# narvi-ctrl.net
KiCad netlist of a schematic drawn in EAGLE
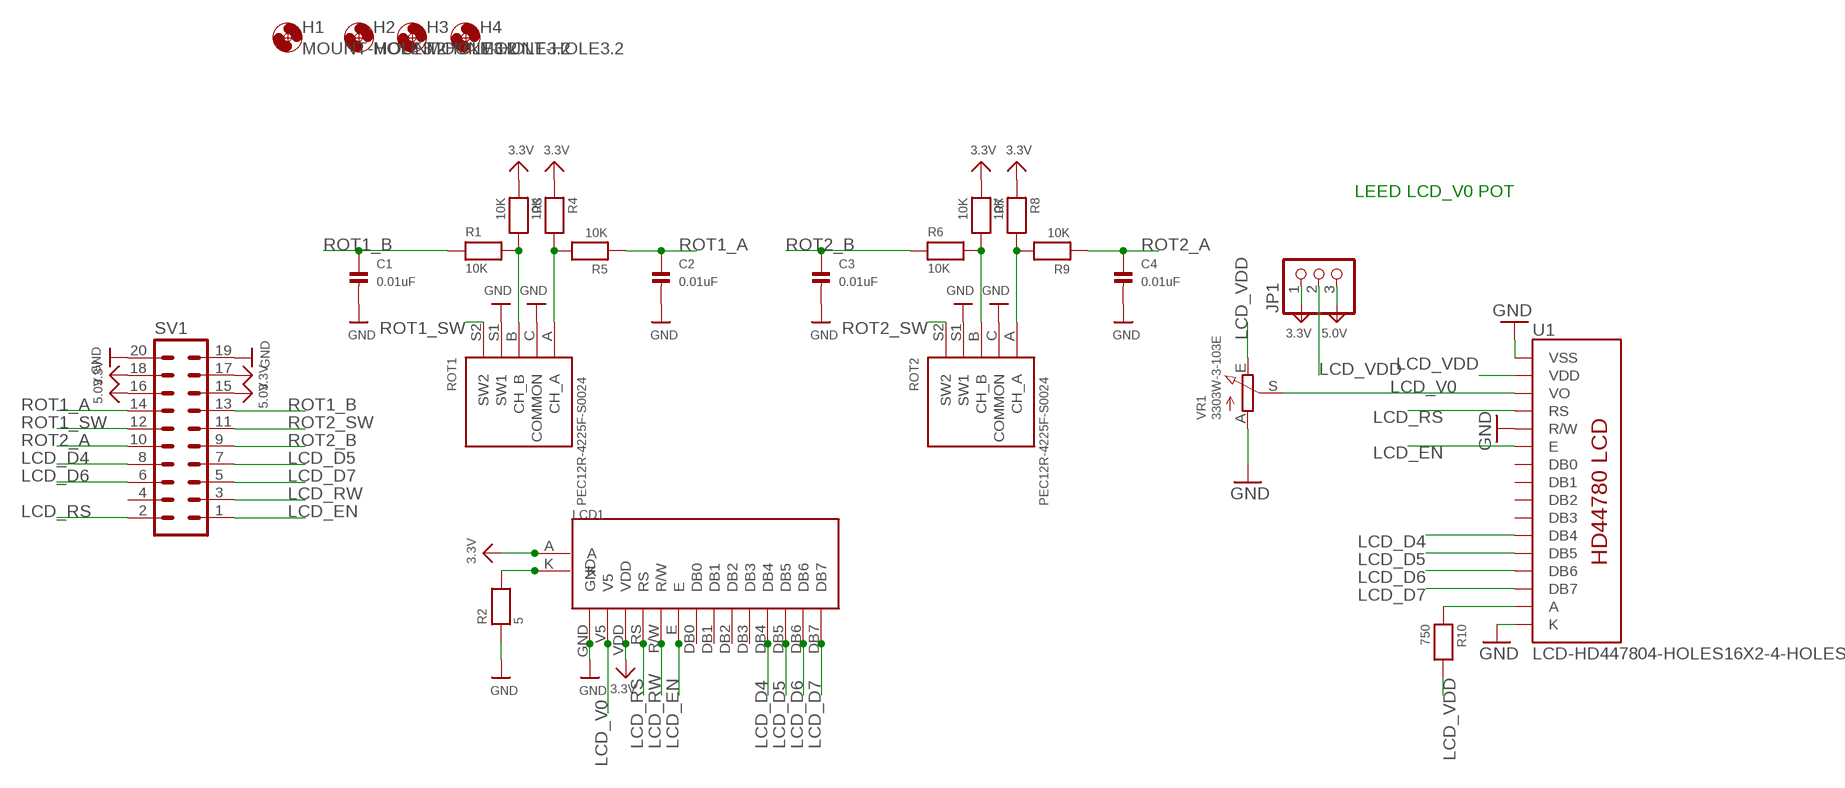
[diagram p0: schematic, sheet 1]

(export (version "E")
  (design (tool "Eeschema 10.0.6"))
  (components
    (comp (ref "C1")
      (value "0.01uF")
      (footprint "eagle-import:0805")
      (libsource (lib "eagle-import") (part "CAP_CERAMIC0805"))
    )
    (comp (ref "C2")
      (value "0.01uF")
      (footprint "eagle-import:0805")
      (libsource (lib "eagle-import") (part "CAP_CERAMIC0805"))
    )
    (comp (ref "C3")
      (value "0.01uF")
      (footprint "eagle-import:0805")
      (libsource (lib "eagle-import") (part "CAP_CERAMIC0805"))
    )
    (comp (ref "C4")
      (value "0.01uF")
      (footprint "eagle-import:0805")
      (libsource (lib "eagle-import") (part "CAP_CERAMIC0805"))
    )
    (comp (ref "H1")
      (value "MOUNT-HOLE3.2")
      (footprint "eagle-import:3,2")
      (libsource (lib "eagle-import") (part "MOUNT-HOLE3.2"))
    )
    (comp (ref "H2")
      (value "MOUNT-HOLE3.2")
      (footprint "eagle-import:3,2")
      (libsource (lib "eagle-import") (part "MOUNT-HOLE3.2"))
    )
    (comp (ref "H3")
      (value "MOUNT-HOLE3.2")
      (footprint "eagle-import:3,2")
      (libsource (lib "eagle-import") (part "MOUNT-HOLE3.2"))
    )
    (comp (ref "H4")
      (value "MOUNT-HOLE3.2")
      (footprint "eagle-import:3,2")
      (libsource (lib "eagle-import") (part "MOUNT-HOLE3.2"))
    )
    (comp (ref "JP1")
      (value "PINHD-1X3")
      (footprint "eagle-import:1X03")
      (libsource (lib "eagle-import") (part "PINHD-1X3"))
    )
    (comp (ref "LCD1")
      (value "NHD-C0220AA-FSW-FTW")
      (footprint "eagle-import:NHD-C0220AA-FSW-FTW")
      (libsource (lib "eagle-import") (part "NHD-C0220AA-FSW-FTW"))
    )
    (comp (ref "R1")
      (value "10K")
      (footprint "eagle-import:_0805")
      (libsource (lib "eagle-import") (part "RESISTOR_0805"))
    )
    (comp (ref "R2")
      (value "5")
      (footprint "eagle-import:_0805")
      (libsource (lib "eagle-import") (part "RESISTOR_0805"))
    )
    (comp (ref "R3")
      (value "10K")
      (footprint "eagle-import:_0805")
      (libsource (lib "eagle-import") (part "RESISTOR_0805"))
    )
    (comp (ref "R4")
      (value "10K")
      (footprint "eagle-import:_0805")
      (libsource (lib "eagle-import") (part "RESISTOR_0805"))
    )
    (comp (ref "R5")
      (value "10K")
      (footprint "eagle-import:_0805")
      (libsource (lib "eagle-import") (part "RESISTOR_0805"))
    )
    (comp (ref "R6")
      (value "10K")
      (footprint "eagle-import:_0805")
      (libsource (lib "eagle-import") (part "RESISTOR_0805"))
    )
    (comp (ref "R7")
      (value "10K")
      (footprint "eagle-import:_0805")
      (libsource (lib "eagle-import") (part "RESISTOR_0805"))
    )
    (comp (ref "R8")
      (value "10K")
      (footprint "eagle-import:_0805")
      (libsource (lib "eagle-import") (part "RESISTOR_0805"))
    )
    (comp (ref "R9")
      (value "10K")
      (footprint "eagle-import:_0805")
      (libsource (lib "eagle-import") (part "RESISTOR_0805"))
    )
    (comp (ref "R10")
      (value "750")
      (footprint "eagle-import:_0805")
      (libsource (lib "eagle-import") (part "RESISTOR_0805"))
    )
    (comp (ref "ROT1")
      (value "PEC12R-4225F-S0024")
      (footprint "eagle-import:PEC111-4XXXK-SXXXX")
      (libsource (lib "eagle-import") (part "PEC11-4215K-S0024"))
    )
    (comp (ref "ROT2")
      (value "PEC12R-4225F-S0024")
      (footprint "eagle-import:PEC111-4XXXK-SXXXX")
      (libsource (lib "eagle-import") (part "PEC11-4215K-S0024"))
    )
    (comp (ref "SV1")
      (value "ML203MSMT")
      (footprint "eagle-import:ML20SMT")
      (fields (field (name "PARTNO") "D2520-6V0C-AR-WE "))
      (libsource (lib "eagle-import") (part "ML203MSMT"))
    )
    (comp (ref "U1")
      (value "LCD-HD447804-HOLES16X2-4-HOLES")
      (footprint "eagle-import:LCD-16X2-4HOLES")
      (libsource (lib "eagle-import") (part "LCD-HD4478016X2-4-HOLES4-HOLES"))
    )
    (comp (ref "VR1")
      (value "3303W-3-103E")
      (footprint "eagle-import:TRIMPOT_BOURNS3MM")
      (libsource (lib "eagle-import") (part "TRIMPOT10K_BOURNS"))
    )
  )
  (nets
    (net (code "1") (name "/LCD_D4") (class "Default")
      (node (ref "LCD1") (pin "DB4") (pinfunction "DB4_DB4") (pintype "bidirectional"))
      (node (ref "SV1") (pin "8") (pinfunction "8_8") (pintype "passive"))
      (node (ref "U1") (pin "11") (pinfunction "DB4_11") (pintype "bidirectional"))
    )
    (net (code "2") (name "/LCD_D5") (class "Default")
      (node (ref "LCD1") (pin "DB5") (pinfunction "DB5_DB5") (pintype "bidirectional"))
      (node (ref "SV1") (pin "7") (pinfunction "7_7") (pintype "passive"))
      (node (ref "U1") (pin "12") (pinfunction "DB5_12") (pintype "bidirectional"))
    )
    (net (code "3") (name "/LCD_D6") (class "Default")
      (node (ref "LCD1") (pin "DB6") (pinfunction "DB6_DB6") (pintype "bidirectional"))
      (node (ref "SV1") (pin "6") (pinfunction "6_6") (pintype "passive"))
      (node (ref "U1") (pin "13") (pinfunction "DB6_13") (pintype "bidirectional"))
    )
    (net (code "4") (name "/LCD_D7") (class "Default")
      (node (ref "LCD1") (pin "DB7") (pinfunction "DB7_DB7") (pintype "bidirectional"))
      (node (ref "SV1") (pin "5") (pinfunction "5_5") (pintype "passive"))
      (node (ref "U1") (pin "14") (pinfunction "DB7_14") (pintype "bidirectional"))
    )
    (net (code "5") (name "/LCD_EN") (class "Default")
      (node (ref "LCD1") (pin "E") (pinfunction "E_E") (pintype "bidirectional"))
      (node (ref "SV1") (pin "1") (pinfunction "1_1") (pintype "passive"))
      (node (ref "U1") (pin "6") (pinfunction "E_6") (pintype "input"))
    )
    (net (code "6") (name "/LCD_RS") (class "Default")
      (node (ref "LCD1") (pin "RS") (pinfunction "RS_RS") (pintype "bidirectional"))
      (node (ref "SV1") (pin "2") (pinfunction "2_2") (pintype "passive"))
      (node (ref "U1") (pin "4") (pinfunction "RS_4") (pintype "input"))
    )
    (net (code "7") (name "/LCD_RW") (class "Default")
      (node (ref "LCD1") (pin "R/W") (pinfunction "R/W_R/W") (pintype "bidirectional"))
      (node (ref "SV1") (pin "3") (pinfunction "3_3") (pintype "passive"))
    )
    (net (code "8") (name "/LCD_V0") (class "Default")
      (node (ref "LCD1") (pin "V5") (pinfunction "V5_V5") (pintype "bidirectional"))
      (node (ref "U1") (pin "3") (pinfunction "VO_3") (pintype "bidirectional"))
      (node (ref "VR1") (pin "S") (pinfunction "S_S") (pintype "passive"))
    )
    (net (code "9") (name "/LCD_VDD") (class "Default")
      (node (ref "JP1") (pin "2") (pinfunction "2_2") (pintype "passive"))
      (node (ref "R10") (pin "2") (pinfunction "2_2") (pintype "passive"))
      (node (ref "U1") (pin "2") (pinfunction "VDD_2") (pintype "power_in"))
      (node (ref "VR1") (pin "E") (pinfunction "E_E") (pintype "passive"))
    )
    (net (code "10") (name "/ROT1_A") (class "Default")
      (node (ref "C2") (pin "1") (pinfunction "P$1_1") (pintype "passive"))
      (node (ref "R5") (pin "1") (pinfunction "1_1") (pintype "passive"))
      (node (ref "SV1") (pin "14") (pinfunction "14_14") (pintype "passive"))
    )
    (net (code "11") (name "/ROT1_B") (class "Default")
      (node (ref "C1") (pin "1") (pinfunction "P$1_1") (pintype "passive"))
      (node (ref "R1") (pin "1") (pinfunction "1_1") (pintype "passive"))
      (node (ref "SV1") (pin "13") (pinfunction "13_13") (pintype "passive"))
    )
    (net (code "12") (name "/ROT1_SW") (class "Default")
      (node (ref "ROT1") (pin "S2") (pinfunction "SW2_S2") (pintype "bidirectional"))
      (node (ref "SV1") (pin "12") (pinfunction "12_12") (pintype "passive"))
    )
    (net (code "13") (name "/ROT2_A") (class "Default")
      (node (ref "C4") (pin "1") (pinfunction "P$1_1") (pintype "passive"))
      (node (ref "R9") (pin "1") (pinfunction "1_1") (pintype "passive"))
      (node (ref "SV1") (pin "10") (pinfunction "10_10") (pintype "passive"))
    )
    (net (code "14") (name "/ROT2_B") (class "Default")
      (node (ref "C3") (pin "1") (pinfunction "P$1_1") (pintype "passive"))
      (node (ref "R6") (pin "1") (pinfunction "1_1") (pintype "passive"))
      (node (ref "SV1") (pin "9") (pinfunction "9_9") (pintype "passive"))
    )
    (net (code "15") (name "/ROT2_SW") (class "Default")
      (node (ref "ROT2") (pin "S2") (pinfunction "SW2_S2") (pintype "bidirectional"))
      (node (ref "SV1") (pin "11") (pinfunction "11_11") (pintype "passive"))
    )
    (net (code "16") (name "3.3V") (class "Default")
      (node (ref "JP1") (pin "1") (pinfunction "1_1") (pintype "passive"))
      (node (ref "LCD1") (pin "A") (pinfunction "A_A") (pintype "bidirectional"))
      (node (ref "LCD1") (pin "VDD") (pinfunction "VDD_VDD") (pintype "bidirectional"))
      (node (ref "R3") (pin "1") (pinfunction "1_1") (pintype "passive"))
      (node (ref "R4") (pin "1") (pinfunction "1_1") (pintype "passive"))
      (node (ref "R7") (pin "1") (pinfunction "1_1") (pintype "passive"))
      (node (ref "R8") (pin "1") (pinfunction "1_1") (pintype "passive"))
      (node (ref "SV1") (pin "17") (pinfunction "17_17") (pintype "passive"))
      (node (ref "SV1") (pin "18") (pinfunction "18_18") (pintype "passive"))
    )
    (net (code "17") (name "5.0V") (class "Default")
      (node (ref "JP1") (pin "3") (pinfunction "3_3") (pintype "passive"))
      (node (ref "SV1") (pin "15") (pinfunction "15_15") (pintype "passive"))
      (node (ref "SV1") (pin "16") (pinfunction "16_16") (pintype "passive"))
    )
    (net (code "18") (name "GND") (class "Default")
      (node (ref "C1") (pin "2") (pinfunction "P$2_2") (pintype "passive"))
      (node (ref "C2") (pin "2") (pinfunction "P$2_2") (pintype "passive"))
      (node (ref "C3") (pin "2") (pinfunction "P$2_2") (pintype "passive"))
      (node (ref "C4") (pin "2") (pinfunction "P$2_2") (pintype "passive"))
      (node (ref "LCD1") (pin "GND") (pinfunction "GND_GND") (pintype "bidirectional"))
      (node (ref "R2") (pin "1") (pinfunction "1_1") (pintype "passive"))
      (node (ref "ROT1") (pin "C") (pinfunction "COMMON_C") (pintype "input"))
      (node (ref "ROT1") (pin "S1") (pinfunction "SW1_S1") (pintype "bidirectional"))
      (node (ref "ROT2") (pin "C") (pinfunction "COMMON_C") (pintype "input"))
      (node (ref "ROT2") (pin "S1") (pinfunction "SW1_S1") (pintype "bidirectional"))
      (node (ref "SV1") (pin "19") (pinfunction "19_19") (pintype "passive"))
      (node (ref "SV1") (pin "20") (pinfunction "20_20") (pintype "passive"))
      (node (ref "U1") (pin "1") (pinfunction "VSS_1") (pintype "power_in"))
      (node (ref "U1") (pin "16") (pinfunction "K_16") (pintype "power_in"))
      (node (ref "U1") (pin "5") (pinfunction "R/W_5") (pintype "input"))
      (node (ref "VR1") (pin "A") (pinfunction "A_A") (pintype "passive"))
    )
    (net (code "19") (name "Net-(LCD1-PadK)") (class "Default")
      (node (ref "LCD1") (pin "K") (pinfunction "K_K") (pintype "bidirectional"))
      (node (ref "R2") (pin "2") (pinfunction "2_2") (pintype "passive"))
    )
    (net (code "20") (name "Net-(ROT1-CH_A)") (class "Default")
      (node (ref "R4") (pin "2") (pinfunction "2_2") (pintype "passive"))
      (node (ref "R5") (pin "2") (pinfunction "2_2") (pintype "passive"))
      (node (ref "ROT1") (pin "A") (pinfunction "CH_A_A") (pintype "output"))
    )
    (net (code "21") (name "Net-(ROT1-CH_B)") (class "Default")
      (node (ref "R1") (pin "2") (pinfunction "2_2") (pintype "passive"))
      (node (ref "R3") (pin "2") (pinfunction "2_2") (pintype "passive"))
      (node (ref "ROT1") (pin "B") (pinfunction "CH_B_B") (pintype "output"))
    )
    (net (code "22") (name "Net-(ROT2-CH_A)") (class "Default")
      (node (ref "R8") (pin "2") (pinfunction "2_2") (pintype "passive"))
      (node (ref "R9") (pin "2") (pinfunction "2_2") (pintype "passive"))
      (node (ref "ROT2") (pin "A") (pinfunction "CH_A_A") (pintype "output"))
    )
    (net (code "23") (name "Net-(ROT2-CH_B)") (class "Default")
      (node (ref "R6") (pin "2") (pinfunction "2_2") (pintype "passive"))
      (node (ref "R7") (pin "2") (pinfunction "2_2") (pintype "passive"))
      (node (ref "ROT2") (pin "B") (pinfunction "CH_B_B") (pintype "output"))
    )
    (net (code "24") (name "Net-(U1-A)") (class "Default")
      (node (ref "R10") (pin "1") (pinfunction "1_1") (pintype "passive"))
      (node (ref "U1") (pin "15") (pinfunction "A_15") (pintype "power_in"))
    )
    (net (code "25") (name "unconnected-(LCD1-PadDB0)") (class "Default")
      (node (ref "LCD1") (pin "DB0") (pinfunction "DB0_DB0") (pintype "bidirectional"))
    )
    (net (code "26") (name "unconnected-(LCD1-PadDB1)") (class "Default")
      (node (ref "LCD1") (pin "DB1") (pinfunction "DB1_DB1") (pintype "bidirectional"))
    )
    (net (code "27") (name "unconnected-(LCD1-PadDB2)") (class "Default")
      (node (ref "LCD1") (pin "DB2") (pinfunction "DB2_DB2") (pintype "bidirectional"))
    )
    (net (code "28") (name "unconnected-(LCD1-PadDB3)") (class "Default")
      (node (ref "LCD1") (pin "DB3") (pinfunction "DB3_DB3") (pintype "bidirectional"))
    )
    (net (code "29") (name "unconnected-(SV1-Pad4)") (class "Default")
      (node (ref "SV1") (pin "4") (pinfunction "4_4") (pintype "passive"))
    )
    (net (code "30") (name "unconnected-(U1-DB0-Pad7)") (class "Default")
      (node (ref "U1") (pin "7") (pinfunction "DB0_7") (pintype "bidirectional"))
    )
    (net (code "31") (name "unconnected-(U1-DB1-Pad8)") (class "Default")
      (node (ref "U1") (pin "8") (pinfunction "DB1_8") (pintype "bidirectional"))
    )
    (net (code "32") (name "unconnected-(U1-DB2-Pad9)") (class "Default")
      (node (ref "U1") (pin "9") (pinfunction "DB2_9") (pintype "bidirectional"))
    )
    (net (code "33") (name "unconnected-(U1-DB3-Pad10)") (class "Default")
      (node (ref "U1") (pin "10") (pinfunction "DB3_10") (pintype "bidirectional"))
    )
  )
)
